# LEDLamp_CapTIvate.net
KiCad netlist of a schematic drawn in EAGLE
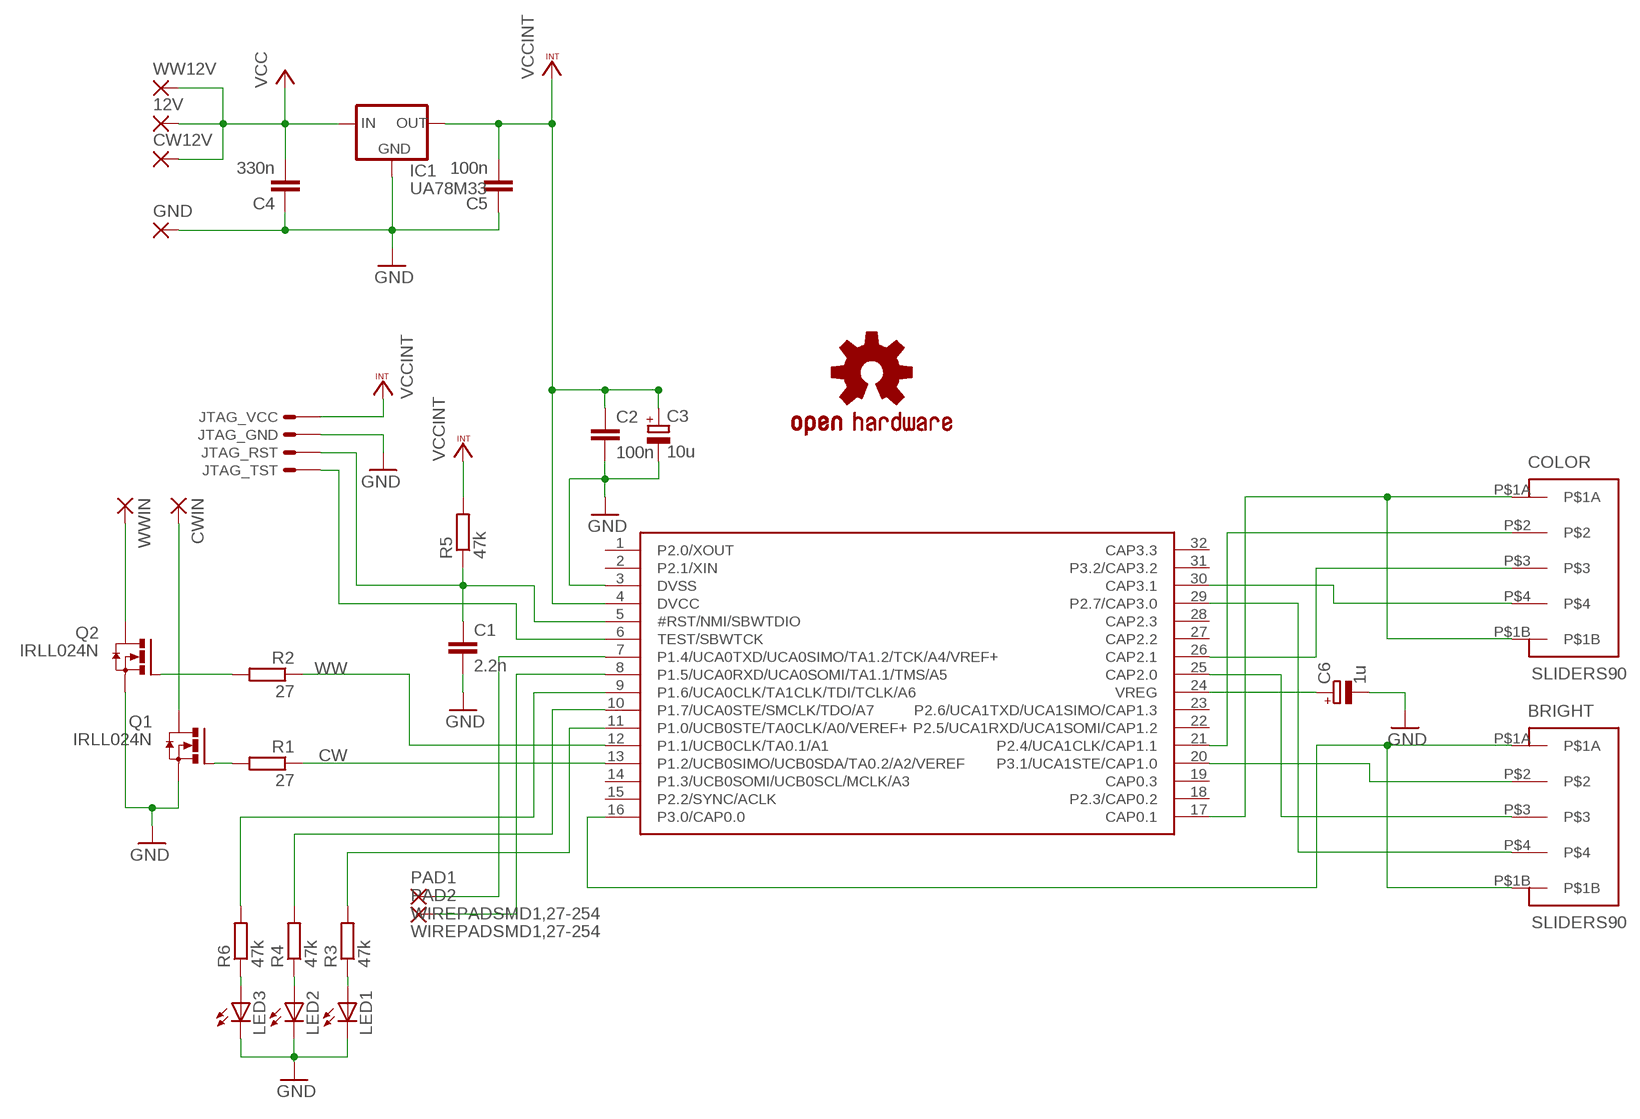
[diagram p0: schematic, sheet 1]

(export (version "E")
  (design (tool "Eeschema 10.0.6"))
  (components
    (comp (ref "12V")
      (value "SMD5")
      (footprint "eagle-import:SMD2,54-5,08")
      (libsource (lib "eagle-import") (part "SMD5"))
    )
    (comp (ref "BRIGHT")
      (value "SLIDERS90")
      (footprint "eagle-import:SLIDER90")
      (libsource (lib "eagle-import") (part "SLIDERS90"))
    )
    (comp (ref "C1")
      (value "2.2n")
      (footprint "eagle-import:C0805")
      (libsource (lib "eagle-import") (part "C-EUC0805"))
    )
    (comp (ref "C2")
      (value "100n")
      (footprint "eagle-import:C0805")
      (libsource (lib "eagle-import") (part "C-EUC0805"))
    )
    (comp (ref "C3")
      (value "10u")
      (footprint "eagle-import:R_2012-12R")
      (libsource (lib "eagle-import") (part "CPOL-EUR/2012-12R"))
    )
    (comp (ref "C4")
      (value "330n")
      (footprint "eagle-import:C0805")
      (libsource (lib "eagle-import") (part "C-EUC0805"))
    )
    (comp (ref "C5")
      (value "100n")
      (footprint "eagle-import:C0805")
      (libsource (lib "eagle-import") (part "C-EUC0805"))
    )
    (comp (ref "C6")
      (value "1u")
      (footprint "eagle-import:R_2012-12R")
      (libsource (lib "eagle-import") (part "CPOL-EUR/2012-12R"))
    )
    (comp (ref "COLOR")
      (value "SLIDERS90")
      (footprint "eagle-import:SLIDER90")
      (libsource (lib "eagle-import") (part "SLIDERS90"))
    )
    (comp (ref "CW12V")
      (value "SMD5")
      (footprint "eagle-import:SMD2,54-5,08")
      (libsource (lib "eagle-import") (part "SMD5"))
    )
    (comp (ref "CWIN")
      (value "SMD5")
      (footprint "eagle-import:SMD2,54-5,08")
      (libsource (lib "eagle-import") (part "SMD5"))
    )
    (comp (ref "GND")
      (value "SMD5")
      (footprint "eagle-import:SMD2,54-5,08")
      (libsource (lib "eagle-import") (part "SMD5"))
    )
    (comp (ref "IC1")
      (value "UA78M33")
      (footprint "eagle-import:SOT223")
      (libsource (lib "eagle-import") (part "UA78M05DCY"))
    )
    (comp (ref "JTAG_")
      (value "MSP430SBWMPE")
      (footprint "eagle-import:MPE-374-04")
      (libsource (lib "eagle-import") (part "MSP430SBWMPE"))
    )
    (comp (ref "LED1")
      (value "LEDTOPLED-SANTANA")
      (footprint "eagle-import:MINI-TOPLED-SANTANA")
      (libsource (lib "eagle-import") (part "LEDTOPLED-SANTANA"))
    )
    (comp (ref "LED2")
      (value "LEDTOPLED-SANTANA")
      (footprint "eagle-import:MINI-TOPLED-SANTANA")
      (libsource (lib "eagle-import") (part "LEDTOPLED-SANTANA"))
    )
    (comp (ref "LED3")
      (value "LEDTOPLED-SANTANA")
      (footprint "eagle-import:MINI-TOPLED-SANTANA")
      (libsource (lib "eagle-import") (part "LEDTOPLED-SANTANA"))
    )
    (comp (ref "MSP430FR2633")
      (value "FR2633")
      (footprint "eagle-import:DA32")
      (libsource (lib "eagle-import") (part "FR2633"))
    )
    (comp (ref "PAD1")
      (value "WIREPADSMD1,27-254")
      (footprint "eagle-import:SMD3X1.5")
      (libsource (lib "eagle-import") (part "WIREPADSMD3X1,5"))
    )
    (comp (ref "PAD2")
      (value "WIREPADSMD1,27-254")
      (footprint "eagle-import:SMD3X1.5")
      (libsource (lib "eagle-import") (part "WIREPADSMD3X1,5"))
    )
    (comp (ref "Q1")
      (value "IRLL024N")
      (footprint "eagle-import:SOT223")
      (libsource (lib "eagle-import") (part "N-HEXFET-2D_?-SOT232"))
    )
    (comp (ref "Q2")
      (value "IRLL024N")
      (footprint "eagle-import:SOT223")
      (libsource (lib "eagle-import") (part "N-HEXFET-2D_?-SOT232"))
    )
    (comp (ref "R1")
      (value "27")
      (footprint "eagle-import:R0805")
      (libsource (lib "eagle-import") (part "R-EU_R0805"))
    )
    (comp (ref "R2")
      (value "27")
      (footprint "eagle-import:R0805")
      (libsource (lib "eagle-import") (part "R-EU_R0805"))
    )
    (comp (ref "R3")
      (value "47k")
      (footprint "eagle-import:R0805")
      (libsource (lib "eagle-import") (part "R-EU_R0805"))
    )
    (comp (ref "R4")
      (value "47k")
      (footprint "eagle-import:R0805")
      (libsource (lib "eagle-import") (part "R-EU_R0805"))
    )
    (comp (ref "R5")
      (value "47k")
      (footprint "eagle-import:R0805")
      (libsource (lib "eagle-import") (part "R-EU_R0805"))
    )
    (comp (ref "R6")
      (value "47k")
      (footprint "eagle-import:R0805")
      (libsource (lib "eagle-import") (part "R-EU_R0805"))
    )
    (comp (ref "U$2")
      (value "OSHW_LOGO_SYMM")
      (footprint "eagle-import:OSHW_LOGO_MED_SYM")
      (libsource (lib "eagle-import") (part "OSHW_LOGO_SYMM"))
    )
    (comp (ref "WW12V")
      (value "SMD5")
      (footprint "eagle-import:SMD2,54-5,08")
      (libsource (lib "eagle-import") (part "SMD5"))
    )
    (comp (ref "WWIN")
      (value "SMD5")
      (footprint "eagle-import:SMD2,54-5,08")
      (libsource (lib "eagle-import") (part "SMD5"))
    )
  )
  (nets
    (net (code "1") (name "/CW") (class "Default")
      (node (ref "MSP430FR2633") (pin "13") (pinfunction "P1.2/UCB0SIMO/UCB0SDA/TA0.2/A2/VEREF_13") (pintype "bidirectional"))
      (node (ref "R1") (pin "1") (pinfunction "1_1") (pintype "passive"))
    )
    (net (code "2") (name "/WW") (class "Default")
      (node (ref "MSP430FR2633") (pin "12") (pinfunction "P1.1/UCB0CLK/TA0.1/A1_12") (pintype "bidirectional"))
      (node (ref "R2") (pin "1") (pinfunction "1_1") (pintype "passive"))
    )
    (net (code "3") (name "GND") (class "Default")
      (node (ref "C1") (pin "2") (pinfunction "2_2") (pintype "passive"))
      (node (ref "C2") (pin "2") (pinfunction "2_2") (pintype "passive"))
      (node (ref "C3") (pin "-") (pinfunction "-_-") (pintype "passive"))
      (node (ref "C4") (pin "1") (pinfunction "1_1") (pintype "passive"))
      (node (ref "C5") (pin "1") (pinfunction "1_1") (pintype "passive"))
      (node (ref "C6") (pin "-") (pinfunction "-_-") (pintype "passive"))
      (node (ref "GND") (pin "1") (pinfunction "P_1") (pintype "passive"))
      (node (ref "IC1") (pin "2") (pinfunction "GND_2") (pintype "input"))
      (node (ref "JTAG_") (pin "P$2") (pinfunction "S_P$2") (pintype "passive"))
      (node (ref "LED1") (pin "C") (pinfunction "C_C") (pintype "passive"))
      (node (ref "LED2") (pin "C") (pinfunction "C_C") (pintype "passive"))
      (node (ref "LED3") (pin "C") (pinfunction "C_C") (pintype "passive"))
      (node (ref "MSP430FR2633") (pin "3") (pinfunction "DVSS_3") (pintype "bidirectional"))
      (node (ref "Q1") (pin "3") (pinfunction "S_3") (pintype "passive"))
      (node (ref "Q2") (pin "3") (pinfunction "S_3") (pintype "passive"))
    )
    (net (code "4") (name "Net-(CWIN-P)") (class "Default")
      (node (ref "CWIN") (pin "1") (pinfunction "P_1") (pintype "passive"))
      (node (ref "Q1") (pin "2") (pinfunction "D_2") (pintype "passive"))
      (node (ref "Q1") (pin "4") (pinfunction "D_4") (pintype "passive"))
    )
    (net (code "5") (name "Net-(JTAG_B-S)") (class "Default")
      (node (ref "C1") (pin "1") (pinfunction "1_1") (pintype "passive"))
      (node (ref "JTAG_") (pin "P$3") (pinfunction "S_P$3") (pintype "passive"))
      (node (ref "MSP430FR2633") (pin "5") (pinfunction "#RST/NMI/SBWTDIO_5") (pintype "bidirectional"))
      (node (ref "R5") (pin "1") (pinfunction "1_1") (pintype "passive"))
    )
    (net (code "6") (name "Net-(JTAG_C-S)") (class "Default")
      (node (ref "JTAG_") (pin "P$4") (pinfunction "S_P$4") (pintype "passive"))
      (node (ref "MSP430FR2633") (pin "6") (pinfunction "TEST/SBWTCK_6") (pintype "bidirectional"))
    )
    (net (code "7") (name "Net-(LED1-PadA)") (class "Default")
      (node (ref "LED1") (pin "A") (pinfunction "A_A") (pintype "passive"))
      (node (ref "R3") (pin "1") (pinfunction "1_1") (pintype "passive"))
    )
    (net (code "8") (name "Net-(LED2-PadA)") (class "Default")
      (node (ref "LED2") (pin "A") (pinfunction "A_A") (pintype "passive"))
      (node (ref "R4") (pin "1") (pinfunction "1_1") (pintype "passive"))
    )
    (net (code "9") (name "Net-(LED3-PadA)") (class "Default")
      (node (ref "LED3") (pin "A") (pinfunction "A_A") (pintype "passive"))
      (node (ref "R6") (pin "1") (pinfunction "1_1") (pintype "passive"))
    )
    (net (code "10") (name "Net-(MSP430FR2633-CAP0.1)") (class "Default")
      (node (ref "COLOR") (pin "P$1A") (pinfunction "P$1A_P$1A") (pintype "bidirectional"))
      (node (ref "COLOR") (pin "P$1B") (pinfunction "P$1B_P$1B") (pintype "bidirectional"))
      (node (ref "MSP430FR2633") (pin "17") (pinfunction "CAP0.1_17") (pintype "bidirectional"))
    )
    (net (code "11") (name "Net-(MSP430FR2633-CAP2.0)") (class "Default")
      (node (ref "BRIGHT") (pin "P$3") (pinfunction "P$3_P$3") (pintype "bidirectional"))
      (node (ref "MSP430FR2633") (pin "25") (pinfunction "CAP2.0_25") (pintype "bidirectional"))
    )
    (net (code "12") (name "Net-(MSP430FR2633-CAP2.1)") (class "Default")
      (node (ref "COLOR") (pin "P$3") (pinfunction "P$3_P$3") (pintype "bidirectional"))
      (node (ref "MSP430FR2633") (pin "26") (pinfunction "CAP2.1_26") (pintype "bidirectional"))
    )
    (net (code "13") (name "Net-(MSP430FR2633-CAP3.1)") (class "Default")
      (node (ref "COLOR") (pin "P$4") (pinfunction "P$4_P$4") (pintype "bidirectional"))
      (node (ref "MSP430FR2633") (pin "30") (pinfunction "CAP3.1_30") (pintype "bidirectional"))
    )
    (net (code "14") (name "Net-(MSP430FR2633-P1.0{slash}UCB0STE{slash}TA0CLK{slash}A0{slash}VEREF+)") (class "Default")
      (node (ref "MSP430FR2633") (pin "11") (pinfunction "P1.0/UCB0STE/TA0CLK/A0/VEREF+_11") (pintype "bidirectional"))
      (node (ref "R3") (pin "2") (pinfunction "2_2") (pintype "passive"))
    )
    (net (code "15") (name "Net-(MSP430FR2633-P1.4{slash}UCA0TXD{slash}UCA0SIMO{slash}TA1.2{slash}TCK{slash}A4{slash}VREF+)") (class "Default")
      (node (ref "MSP430FR2633") (pin "7") (pinfunction "P1.4/UCA0TXD/UCA0SIMO/TA1.2/TCK/A4/VREF+_7") (pintype "bidirectional"))
      (node (ref "PAD1") (pin "P$1") (pinfunction "P_P$1") (pintype "passive"))
    )
    (net (code "16") (name "Net-(MSP430FR2633-P1.5{slash}UCA0RXD{slash}UCA0SOMI{slash}TA1.1{slash}TMS{slash}A5)") (class "Default")
      (node (ref "MSP430FR2633") (pin "8") (pinfunction "P1.5/UCA0RXD/UCA0SOMI/TA1.1/TMS/A5_8") (pintype "bidirectional"))
      (node (ref "PAD2") (pin "P$1") (pinfunction "P_P$1") (pintype "passive"))
    )
    (net (code "17") (name "Net-(MSP430FR2633-P1.6{slash}UCA0CLK{slash}TA1CLK{slash}TDI{slash}TCLK{slash}A6)") (class "Default")
      (node (ref "MSP430FR2633") (pin "9") (pinfunction "P1.6/UCA0CLK/TA1CLK/TDI/TCLK/A6_9") (pintype "bidirectional"))
      (node (ref "R6") (pin "2") (pinfunction "2_2") (pintype "passive"))
    )
    (net (code "18") (name "Net-(MSP430FR2633-P1.7{slash}UCA0STE{slash}SMCLK{slash}TDO{slash}A7)") (class "Default")
      (node (ref "MSP430FR2633") (pin "10") (pinfunction "P1.7/UCA0STE/SMCLK/TDO/A7_10") (pintype "bidirectional"))
      (node (ref "R4") (pin "2") (pinfunction "2_2") (pintype "passive"))
    )
    (net (code "19") (name "Net-(MSP430FR2633-P2.4{slash}UCA1CLK{slash}CAP1.1)") (class "Default")
      (node (ref "COLOR") (pin "P$2") (pinfunction "P$2_P$2") (pintype "bidirectional"))
      (node (ref "MSP430FR2633") (pin "21") (pinfunction "P2.4/UCA1CLK/CAP1.1_21") (pintype "bidirectional"))
    )
    (net (code "20") (name "Net-(MSP430FR2633-P2.7{slash}CAP3.0)") (class "Default")
      (node (ref "BRIGHT") (pin "P$4") (pinfunction "P$4_P$4") (pintype "bidirectional"))
      (node (ref "MSP430FR2633") (pin "29") (pinfunction "P2.7/CAP3.0_29") (pintype "bidirectional"))
    )
    (net (code "21") (name "Net-(MSP430FR2633-P3.0{slash}CAP0.0)") (class "Default")
      (node (ref "BRIGHT") (pin "P$1A") (pinfunction "P$1A_P$1A") (pintype "bidirectional"))
      (node (ref "BRIGHT") (pin "P$1B") (pinfunction "P$1B_P$1B") (pintype "bidirectional"))
      (node (ref "MSP430FR2633") (pin "16") (pinfunction "P3.0/CAP0.0_16") (pintype "bidirectional"))
    )
    (net (code "22") (name "Net-(MSP430FR2633-P3.1{slash}UCA1STE{slash}CAP1.0)") (class "Default")
      (node (ref "BRIGHT") (pin "P$2") (pinfunction "P$2_P$2") (pintype "bidirectional"))
      (node (ref "MSP430FR2633") (pin "20") (pinfunction "P3.1/UCA1STE/CAP1.0_20") (pintype "bidirectional"))
    )
    (net (code "23") (name "Net-(MSP430FR2633-VREG)") (class "Default")
      (node (ref "C6") (pin "+") (pinfunction "+_+") (pintype "passive"))
      (node (ref "MSP430FR2633") (pin "24") (pinfunction "VREG_24") (pintype "bidirectional"))
    )
    (net (code "24") (name "Net-(Q1-G)") (class "Default")
      (node (ref "Q1") (pin "1") (pinfunction "G_1") (pintype "passive"))
      (node (ref "R1") (pin "2") (pinfunction "2_2") (pintype "passive"))
    )
    (net (code "25") (name "Net-(Q2-G)") (class "Default")
      (node (ref "Q2") (pin "1") (pinfunction "G_1") (pintype "passive"))
      (node (ref "R2") (pin "2") (pinfunction "2_2") (pintype "passive"))
    )
    (net (code "26") (name "Net-(WWIN-P)") (class "Default")
      (node (ref "Q2") (pin "2") (pinfunction "D_2") (pintype "passive"))
      (node (ref "Q2") (pin "4") (pinfunction "D_4") (pintype "passive"))
      (node (ref "WWIN") (pin "1") (pinfunction "P_1") (pintype "passive"))
    )
    (net (code "27") (name "VCC") (class "Default")
      (node (ref "12V") (pin "1") (pinfunction "P_1") (pintype "passive"))
      (node (ref "C4") (pin "2") (pinfunction "2_2") (pintype "passive"))
      (node (ref "CW12V") (pin "1") (pinfunction "P_1") (pintype "passive"))
      (node (ref "IC1") (pin "1") (pinfunction "IN_1") (pintype "input"))
      (node (ref "WW12V") (pin "1") (pinfunction "P_1") (pintype "passive"))
    )
    (net (code "28") (name "VCCINT") (class "Default")
      (node (ref "C2") (pin "1") (pinfunction "1_1") (pintype "passive"))
      (node (ref "C3") (pin "+") (pinfunction "+_+") (pintype "passive"))
      (node (ref "C5") (pin "2") (pinfunction "2_2") (pintype "passive"))
      (node (ref "IC1") (pin "3") (pinfunction "OUT_3") (pintype "passive"))
      (node (ref "JTAG_") (pin "P$1") (pinfunction "S_P$1") (pintype "passive"))
      (node (ref "MSP430FR2633") (pin "4") (pinfunction "DVCC_4") (pintype "bidirectional"))
      (node (ref "R5") (pin "2") (pinfunction "2_2") (pintype "passive"))
    )
    (net (code "29") (name "unconnected-(MSP430FR2633-CAP0.3-Pad19)") (class "Default")
      (node (ref "MSP430FR2633") (pin "19") (pinfunction "CAP0.3_19") (pintype "bidirectional"))
    )
    (net (code "30") (name "unconnected-(MSP430FR2633-CAP2.2-Pad27)") (class "Default")
      (node (ref "MSP430FR2633") (pin "27") (pinfunction "CAP2.2_27") (pintype "bidirectional"))
    )
    (net (code "31") (name "unconnected-(MSP430FR2633-CAP2.3-Pad28)") (class "Default")
      (node (ref "MSP430FR2633") (pin "28") (pinfunction "CAP2.3_28") (pintype "bidirectional"))
    )
    (net (code "32") (name "unconnected-(MSP430FR2633-CAP3.3-Pad32)") (class "Default")
      (node (ref "MSP430FR2633") (pin "32") (pinfunction "CAP3.3_32") (pintype "bidirectional"))
    )
    (net (code "33") (name "unconnected-(MSP430FR2633-P1.3{slash}UCB0SOMI{slash}UCB0SCL{slash}MCLK{slash}A3-Pad14)") (class "Default")
      (node (ref "MSP430FR2633") (pin "14") (pinfunction "P1.3/UCB0SOMI/UCB0SCL/MCLK/A3_14") (pintype "bidirectional"))
    )
    (net (code "34") (name "unconnected-(MSP430FR2633-P2.0{slash}XOUT-Pad1)") (class "Default")
      (node (ref "MSP430FR2633") (pin "1") (pinfunction "P2.0/XOUT_1") (pintype "bidirectional"))
    )
    (net (code "35") (name "unconnected-(MSP430FR2633-P2.1{slash}XIN-Pad2)") (class "Default")
      (node (ref "MSP430FR2633") (pin "2") (pinfunction "P2.1/XIN_2") (pintype "bidirectional"))
    )
    (net (code "36") (name "unconnected-(MSP430FR2633-P2.2{slash}SYNC{slash}ACLK-Pad15)") (class "Default")
      (node (ref "MSP430FR2633") (pin "15") (pinfunction "P2.2/SYNC/ACLK_15") (pintype "bidirectional"))
    )
    (net (code "37") (name "unconnected-(MSP430FR2633-P2.3{slash}CAP0.2-Pad18)") (class "Default")
      (node (ref "MSP430FR2633") (pin "18") (pinfunction "P2.3/CAP0.2_18") (pintype "bidirectional"))
    )
    (net (code "38") (name "unconnected-(MSP430FR2633-P2.5{slash}UCA1RXD{slash}UCA1SOMI{slash}CAP1.2-Pad22)") (class "Default")
      (node (ref "MSP430FR2633") (pin "22") (pinfunction "P2.5/UCA1RXD/UCA1SOMI/CAP1.2_22") (pintype "bidirectional"))
    )
    (net (code "39") (name "unconnected-(MSP430FR2633-P2.6{slash}UCA1TXD{slash}UCA1SIMO{slash}CAP1.3-Pad23)") (class "Default")
      (node (ref "MSP430FR2633") (pin "23") (pinfunction "P2.6/UCA1TXD/UCA1SIMO/CAP1.3_23") (pintype "bidirectional"))
    )
    (net (code "40") (name "unconnected-(MSP430FR2633-P3.2{slash}CAP3.2-Pad31)") (class "Default")
      (node (ref "MSP430FR2633") (pin "31") (pinfunction "P3.2/CAP3.2_31") (pintype "bidirectional"))
    )
  )
)
